# ESP-01_programmer.net
KiCad netlist of a schematic drawn in EAGLE
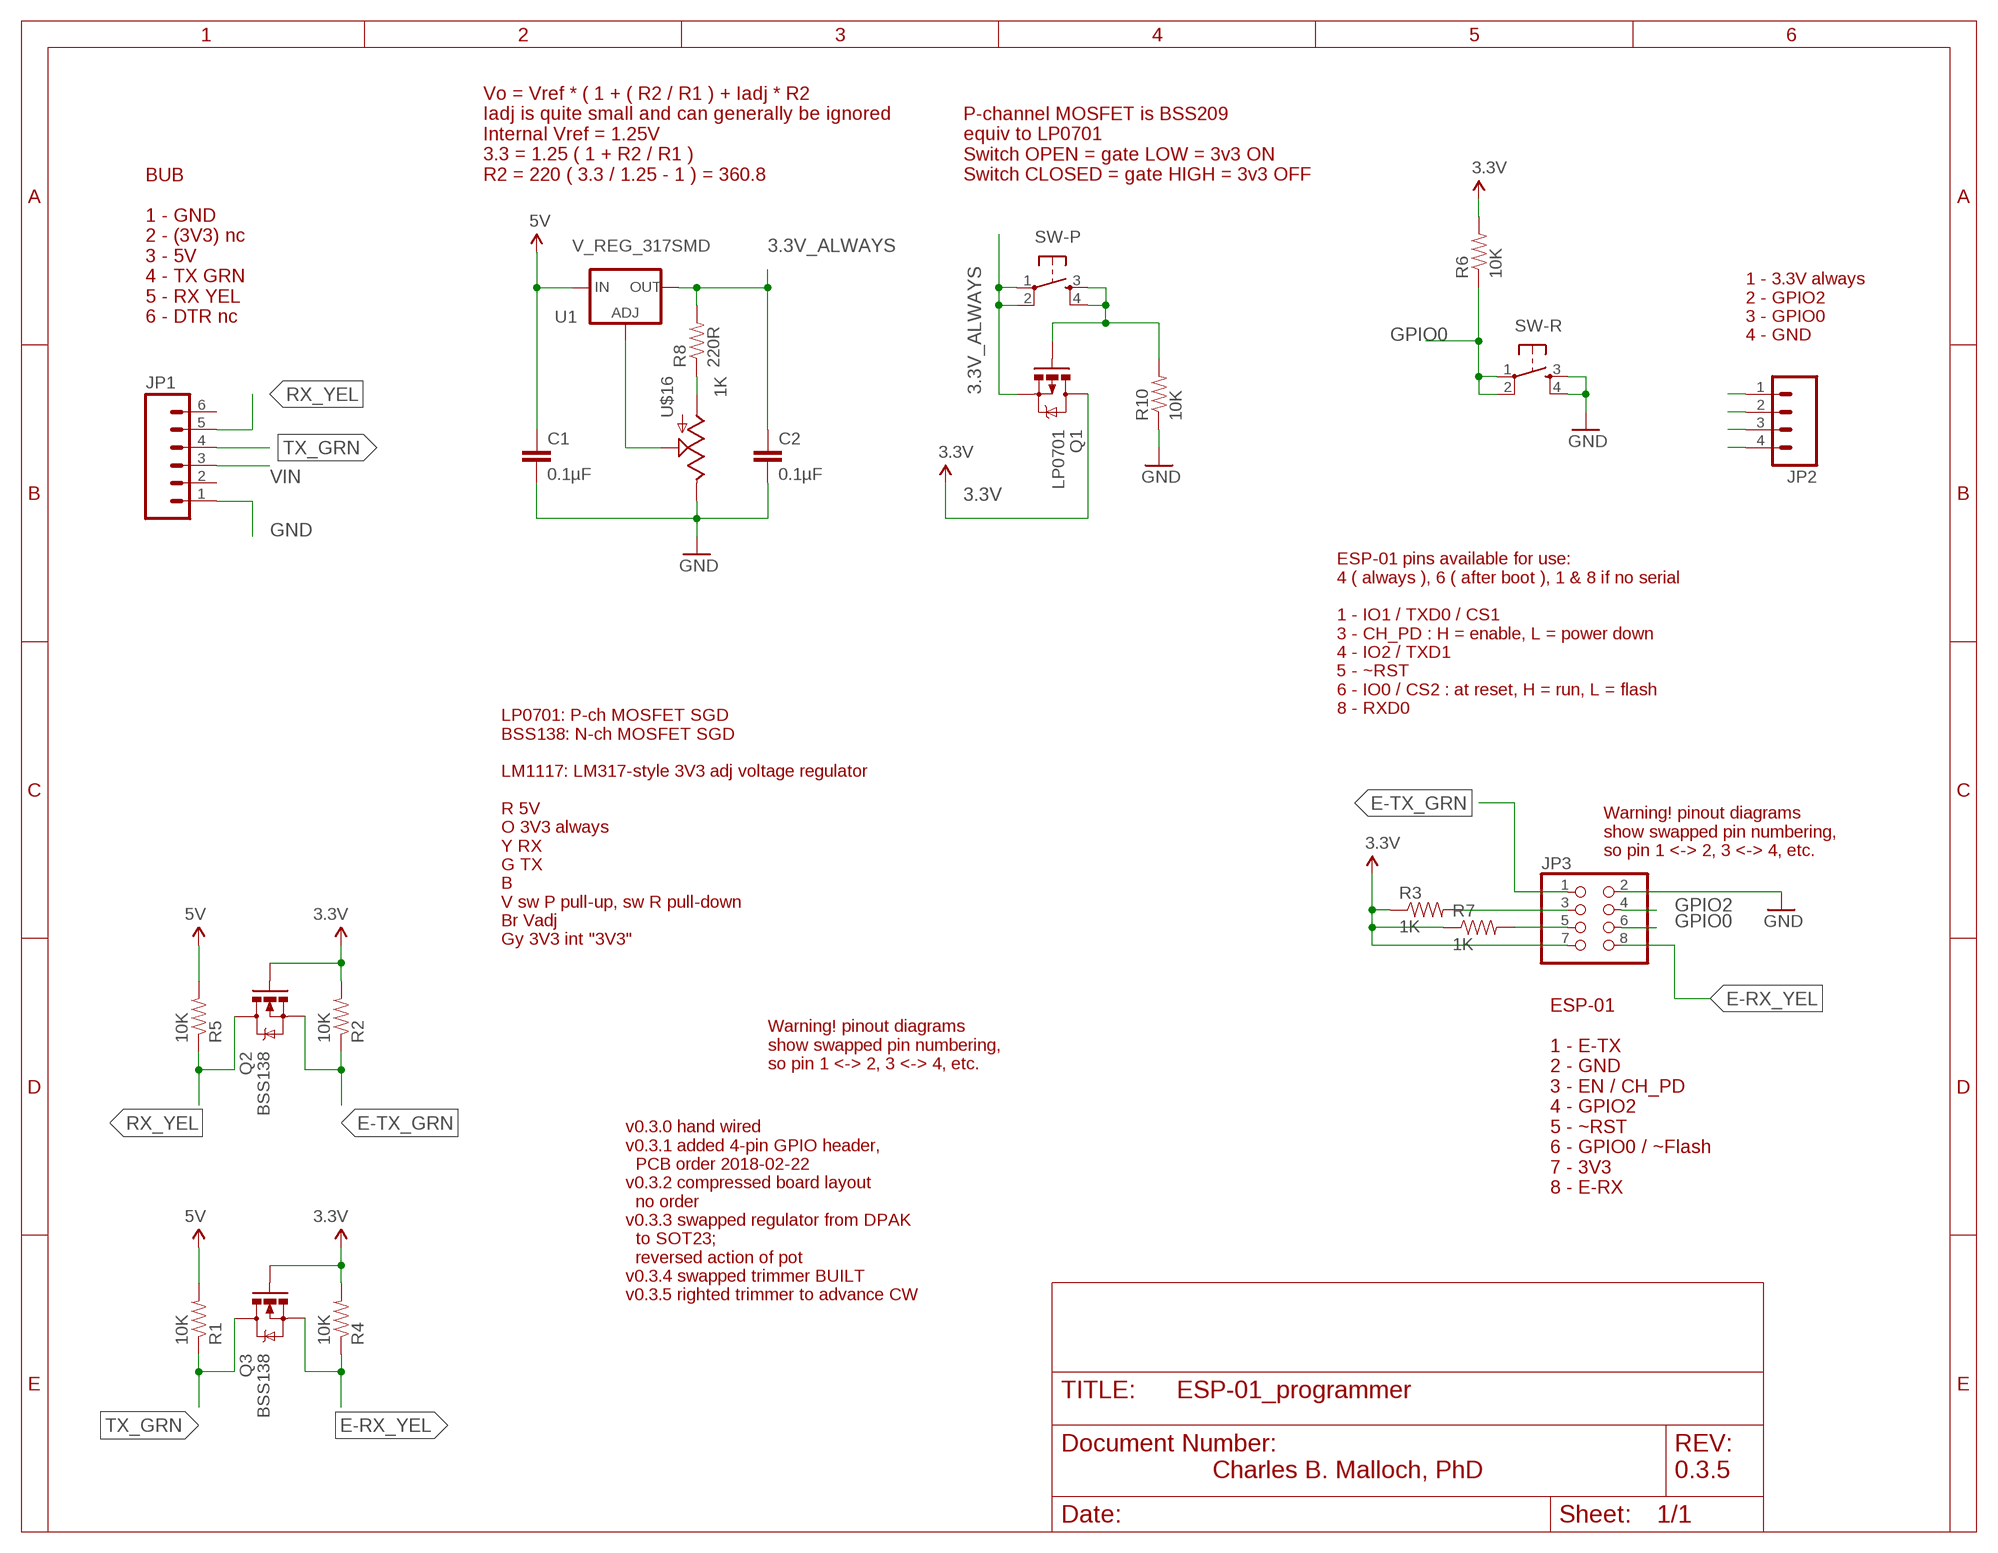
[diagram p0: schematic, sheet 1]

(export (version "E")
  (design (tool "Eeschema 10.0.6"))
  (components
    (comp (ref "C1")
      (value "0.1µF")
      (footprint "eagle-import:1206")
      (libsource (lib "eagle-import") (part "CAP1206"))
    )
    (comp (ref "C2")
      (value "0.1µF")
      (footprint "eagle-import:1206")
      (libsource (lib "eagle-import") (part "CAP1206"))
    )
    (comp (ref "JP1")
      (value "M06LOCK_LONGPADS")
      (footprint "eagle-import:1X06_LOCK_LONGPADS")
      (libsource (lib "eagle-import") (part "M06LOCK_LONGPADS"))
    )
    (comp (ref "JP2")
      (value "M04LOCK_LONGPADS")
      (footprint "eagle-import:1X04_LOCK_LONGPADS")
      (libsource (lib "eagle-import") (part "M04LOCK_LONGPADS"))
    )
    (comp (ref "JP3")
      (value "PINHD-2X4")
      (footprint "eagle-import:2X04")
      (libsource (lib "eagle-import") (part "PINHD-2X4"))
    )
    (comp (ref "Q1")
      (value "LP0701")
      (footprint "eagle-import:SOT23-3")
      (libsource (lib "eagle-import") (part "MOSFET-PCHANNELSMD"))
    )
    (comp (ref "Q2")
      (value "BSS138")
      (footprint "eagle-import:SOT23-3")
      (libsource (lib "eagle-import") (part "BSS138TRANS-00830"))
    )
    (comp (ref "Q3")
      (value "BSS138")
      (footprint "eagle-import:SOT23-3")
      (libsource (lib "eagle-import") (part "BSS138TRANS-00830"))
    )
    (comp (ref "R1")
      (value "10K")
      (footprint "eagle-import:1206")
      (libsource (lib "eagle-import") (part "RESISTOR1206"))
    )
    (comp (ref "R2")
      (value "10K")
      (footprint "eagle-import:1206")
      (libsource (lib "eagle-import") (part "RESISTOR1206"))
    )
    (comp (ref "R3")
      (value "1K")
      (footprint "eagle-import:1206")
      (libsource (lib "eagle-import") (part "RESISTOR1206"))
    )
    (comp (ref "R4")
      (value "10K")
      (footprint "eagle-import:1206")
      (libsource (lib "eagle-import") (part "RESISTOR1206"))
    )
    (comp (ref "R5")
      (value "10K")
      (footprint "eagle-import:1206")
      (libsource (lib "eagle-import") (part "RESISTOR1206"))
    )
    (comp (ref "R6")
      (value "10K")
      (footprint "eagle-import:1206")
      (libsource (lib "eagle-import") (part "RESISTOR1206"))
    )
    (comp (ref "R7")
      (value "1K")
      (footprint "eagle-import:1206")
      (libsource (lib "eagle-import") (part "RESISTOR1206"))
    )
    (comp (ref "R8")
      (value "220R")
      (footprint "eagle-import:1206")
      (libsource (lib "eagle-import") (part "RESISTOR1206"))
    )
    (comp (ref "R10")
      (value "10K")
      (footprint "eagle-import:1206")
      (libsource (lib "eagle-import") (part "RESISTOR1206"))
    )
    (comp (ref "SW-P")
      (value "TAC_SWITCHPTH")
      (footprint "eagle-import:TACTILE-PTH")
      (libsource (lib "eagle-import") (part "TAC_SWITCHPTH"))
    )
    (comp (ref "SW-R")
      (value "TAC_SWITCHPTH")
      (footprint "eagle-import:TACTILE-PTH")
      (libsource (lib "eagle-import") (part "TAC_SWITCHPTH"))
    )
    (comp (ref "U$16")
      (value "1K")
      (footprint "eagle-import:3362U")
      (libsource (lib "eagle-import") (part "POT100K_3362U"))
    )
    (comp (ref "U1")
      (value "V_REG_317SMD")
      (footprint "eagle-import:SOT223")
      (libsource (lib "eagle-import") (part "V_REG_317SMD"))
    )
  )
  (nets
    (net (code "1") (name "/3.3V_ALWAYS") (class "Default")
      (node (ref "C2") (pin "1") (pinfunction "1_1") (pintype "passive"))
      (node (ref "JP2") (pin "1") (pinfunction "1_1") (pintype "passive"))
      (node (ref "Q1") (pin "2") (pinfunction "S_2") (pintype "passive"))
      (node (ref "R8") (pin "2") (pinfunction "2_2") (pintype "passive"))
      (node (ref "SW-P") (pin "1") (pinfunction "1_1") (pintype "passive"))
      (node (ref "SW-P") (pin "2") (pinfunction "2_2") (pintype "passive"))
      (node (ref "U1") (pin "2") (pinfunction "OUT_2") (pintype "output"))
    )
    (net (code "2") (name "/GPIO0") (class "Default")
      (node (ref "JP2") (pin "3") (pinfunction "3_3") (pintype "passive"))
      (node (ref "JP3") (pin "6") (pinfunction "6_6") (pintype "passive"))
      (node (ref "R6") (pin "1") (pinfunction "1_1") (pintype "passive"))
      (node (ref "SW-R") (pin "1") (pinfunction "1_1") (pintype "passive"))
      (node (ref "SW-R") (pin "2") (pinfunction "2_2") (pintype "passive"))
    )
    (net (code "3") (name "/GPIO2") (class "Default")
      (node (ref "JP2") (pin "2") (pinfunction "2_2") (pintype "passive"))
      (node (ref "JP3") (pin "4") (pinfunction "4_4") (pintype "passive"))
    )
    (net (code "4") (name "3.3V") (class "Default")
      (node (ref "JP3") (pin "7") (pinfunction "7_7") (pintype "passive"))
      (node (ref "Q1") (pin "3") (pinfunction "D_3") (pintype "passive"))
      (node (ref "Q2") (pin "1") (pinfunction "G_1") (pintype "passive"))
      (node (ref "Q3") (pin "1") (pinfunction "G_1") (pintype "passive"))
      (node (ref "R2") (pin "2") (pinfunction "2_2") (pintype "passive"))
      (node (ref "R3") (pin "1") (pinfunction "1_1") (pintype "passive"))
      (node (ref "R4") (pin "2") (pinfunction "2_2") (pintype "passive"))
      (node (ref "R6") (pin "2") (pinfunction "2_2") (pintype "passive"))
      (node (ref "R7") (pin "1") (pinfunction "1_1") (pintype "passive"))
    )
    (net (code "5") (name "5V") (class "Default")
      (node (ref "C1") (pin "1") (pinfunction "1_1") (pintype "passive"))
      (node (ref "JP1") (pin "3") (pinfunction "3_3") (pintype "passive"))
      (node (ref "R1") (pin "2") (pinfunction "2_2") (pintype "passive"))
      (node (ref "R5") (pin "2") (pinfunction "2_2") (pintype "passive"))
      (node (ref "U1") (pin "3") (pinfunction "IN_3") (pintype "input"))
    )
    (net (code "6") (name "E-RX_YEL") (class "Default")
      (node (ref "JP3") (pin "8") (pinfunction "8_8") (pintype "passive"))
      (node (ref "Q3") (pin "2") (pinfunction "S_2") (pintype "passive"))
      (node (ref "R4") (pin "1") (pinfunction "1_1") (pintype "passive"))
    )
    (net (code "7") (name "E-TX_GRN") (class "Default")
      (node (ref "JP3") (pin "1") (pinfunction "1_1") (pintype "passive"))
      (node (ref "Q2") (pin "2") (pinfunction "S_2") (pintype "passive"))
      (node (ref "R2") (pin "1") (pinfunction "1_1") (pintype "passive"))
    )
    (net (code "8") (name "GND") (class "Default")
      (node (ref "C1") (pin "2") (pinfunction "2_2") (pintype "passive"))
      (node (ref "C2") (pin "2") (pinfunction "2_2") (pintype "passive"))
      (node (ref "JP1") (pin "1") (pinfunction "1_1") (pintype "passive"))
      (node (ref "JP2") (pin "4") (pinfunction "4_4") (pintype "passive"))
      (node (ref "JP3") (pin "2") (pinfunction "2_2") (pintype "passive"))
      (node (ref "R10") (pin "1") (pinfunction "1_1") (pintype "passive"))
      (node (ref "SW-R") (pin "3") (pinfunction "3_3") (pintype "passive"))
      (node (ref "SW-R") (pin "4") (pinfunction "4_4") (pintype "passive"))
      (node (ref "U$16") (pin "P$1") (pinfunction "E_P$1") (pintype "passive"))
    )
    (net (code "9") (name "Net-(JP3-Pad3)") (class "Default")
      (node (ref "JP3") (pin "3") (pinfunction "3_3") (pintype "passive"))
      (node (ref "R3") (pin "2") (pinfunction "2_2") (pintype "passive"))
    )
    (net (code "10") (name "Net-(JP3-Pad5)") (class "Default")
      (node (ref "JP3") (pin "5") (pinfunction "5_5") (pintype "passive"))
      (node (ref "R7") (pin "2") (pinfunction "2_2") (pintype "passive"))
    )
    (net (code "11") (name "Net-(Q1-G)") (class "Default")
      (node (ref "Q1") (pin "1") (pinfunction "G_1") (pintype "passive"))
      (node (ref "R10") (pin "2") (pinfunction "2_2") (pintype "passive"))
      (node (ref "SW-P") (pin "3") (pinfunction "3_3") (pintype "passive"))
      (node (ref "SW-P") (pin "4") (pinfunction "4_4") (pintype "passive"))
    )
    (net (code "12") (name "Net-(U$16-A)") (class "Default")
      (node (ref "R8") (pin "1") (pinfunction "1_1") (pintype "passive"))
      (node (ref "U$16") (pin "P$3") (pinfunction "A_P$3") (pintype "passive"))
    )
    (net (code "13") (name "Net-(U$16-S)") (class "Default")
      (node (ref "U$16") (pin "P$2") (pinfunction "S_P$2") (pintype "passive"))
      (node (ref "U1") (pin "1") (pinfunction "ADJ_1") (pintype "input"))
    )
    (net (code "14") (name "RX_YEL") (class "Default")
      (node (ref "JP1") (pin "5") (pinfunction "5_5") (pintype "passive"))
      (node (ref "Q2") (pin "3") (pinfunction "D_3") (pintype "passive"))
      (node (ref "R5") (pin "1") (pinfunction "1_1") (pintype "passive"))
    )
    (net (code "15") (name "TX_GRN") (class "Default")
      (node (ref "JP1") (pin "4") (pinfunction "4_4") (pintype "passive"))
      (node (ref "Q3") (pin "3") (pinfunction "D_3") (pintype "passive"))
      (node (ref "R1") (pin "1") (pinfunction "1_1") (pintype "passive"))
    )
    (net (code "16") (name "unconnected-(JP1-Pad2)") (class "Default")
      (node (ref "JP1") (pin "2") (pinfunction "2_2") (pintype "passive"))
    )
    (net (code "17") (name "unconnected-(JP1-Pad6)") (class "Default")
      (node (ref "JP1") (pin "6") (pinfunction "6_6") (pintype "passive"))
    )
  )
)
